# SCH_Weather_Station_2023-01-10.net
KiCad netlist of a schematic drawn in EasyEDA
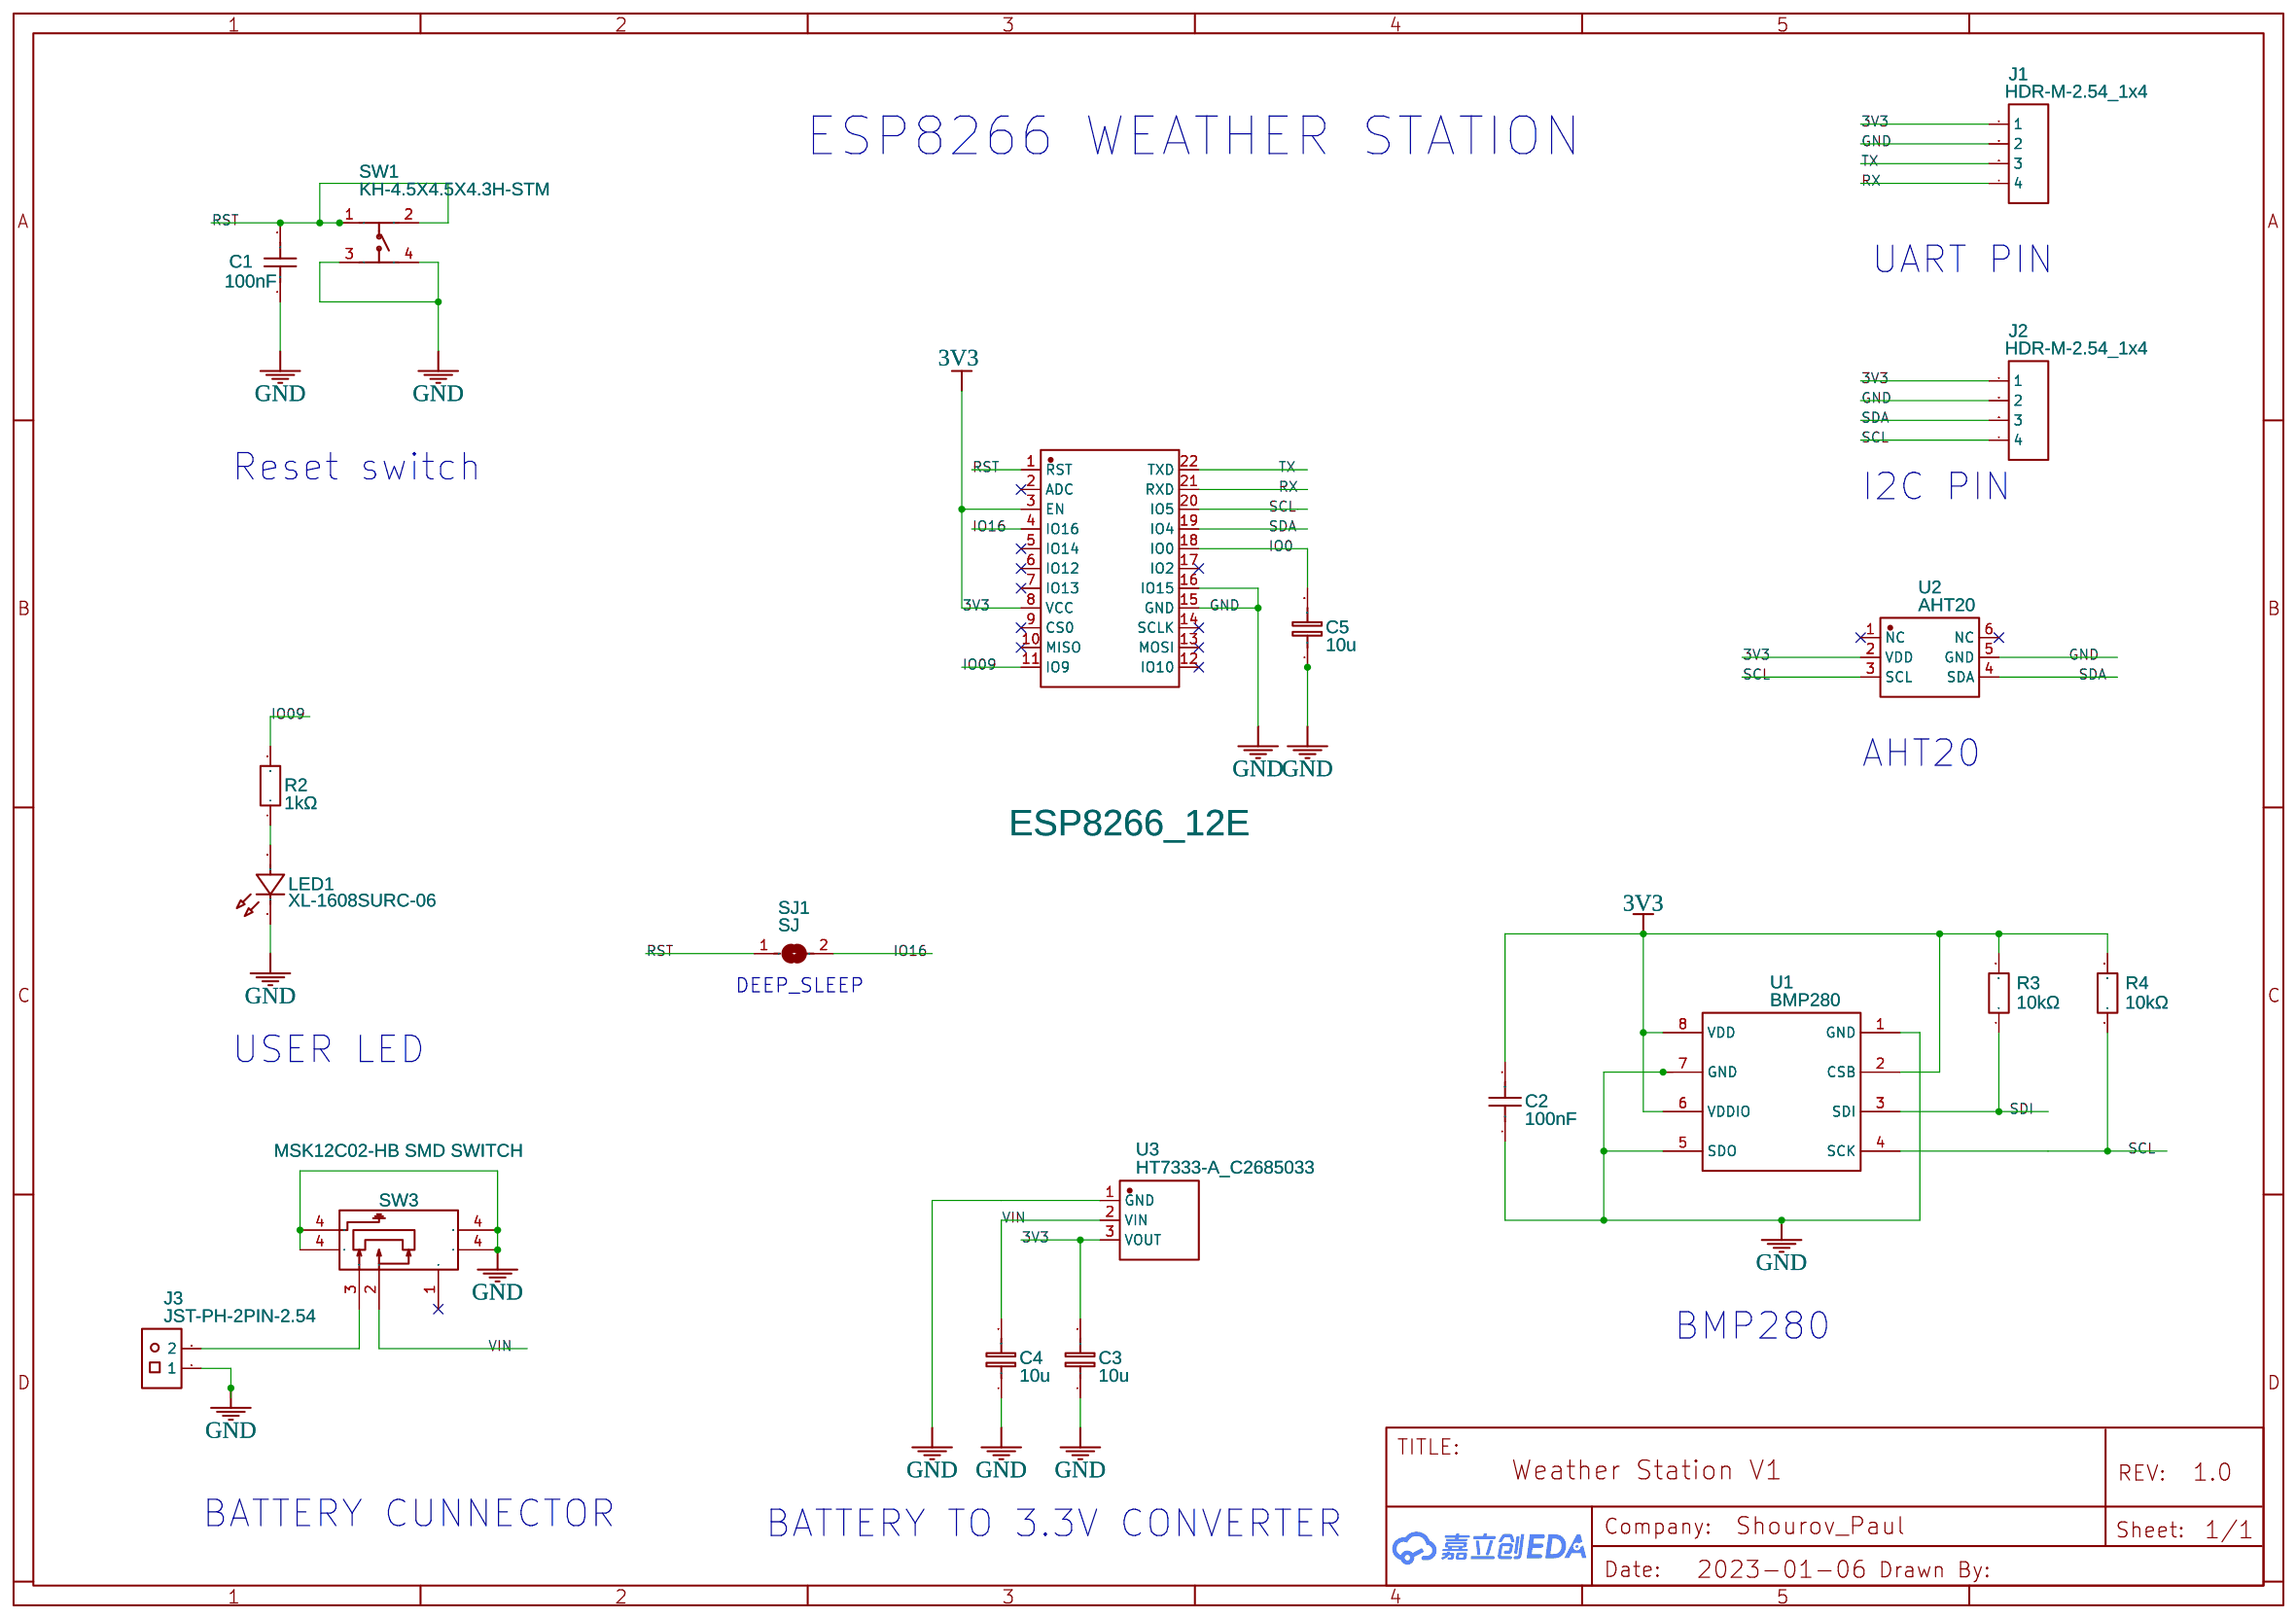
[diagram p0: schematic sheet]

(export (version "E")
  (design (tool "Eeschema 10.0.6"))
  (components
    (comp (ref "C1")
      (value "100nF")
      (fields
        (field (name "BOM_Manufacturer Part") "CC0603KRX7R6BB104")
        (field (name "BOM_Supplier Part") "C519438")
      )
      (libsource (lib "") (part "CC0603KRX7R6BB104"))
    )
    (comp (ref "C2")
      (value "100nF")
      (fields
        (field (name "BOM_Manufacturer Part") "CC0603KRX7R6BB104")
        (field (name "BOM_Supplier Part") "C519438")
      )
      (libsource (lib "") (part "CC0603KRX7R6BB104"))
    )
    (comp (ref "C3") (value "10u") (libsource (lib "") (part "C_0603_EU_2")))
    (comp (ref "C4") (value "10u") (libsource (lib "") (part "C_0603_EU_1")))
    (comp (ref "C5") (value "10u") (libsource (lib "") (part "C_0603_EU")))
    (comp (ref "ESP8266_12E")
      (value "2.4GHz")
      (fields (field (name "BOM_Manufacturer Part") "ESP-12E") (field (name "BOM_Supplier Part") "C89297"))
      (libsource (lib "") (part "ESP-12E"))
    )
    (comp (ref "J1")
      (value "HDR-M-2.54_1x4")
      (fields (field (name "BOM_Supplier Part") "C124378"))
      (libsource (lib "") (part "HDR-M-2.54_1x4"))
    )
    (comp (ref "J2")
      (value "HDR-M-2.54_1x4")
      (fields (field (name "BOM_Supplier Part") "C124378"))
      (libsource (lib "") (part "HDR-M-2.54_1x4"))
    )
    (comp (ref "J3") (value "JST-PH-2PIN-2.54") (libsource (lib "") (part "JST-PH-2PIN-2.54")))
    (comp (ref "LED1")
      (value "XL-1608SURC-06")
      (fields (field (name "BOM_Supplier Part") "C965799"))
      (libsource (lib "") (part "XL-1608SURC-06"))
    )
    (comp (ref "R2")
      (value "1kΩ")
      (fields
        (field (name "BOM_Manufacturer Part") "FRC0603J103TS")
        (field (name "BOM_Supplier Part") "C2930027")
      )
      (libsource (lib "") (part "FRC0603J103TS"))
    )
    (comp (ref "R3")
      (value "10kΩ")
      (fields
        (field (name "BOM_Manufacturer Part") "FRC0603J103TS")
        (field (name "BOM_Supplier Part") "C2930027")
      )
      (libsource (lib "") (part "FRC0603J103TS"))
    )
    (comp (ref "R4")
      (value "10kΩ")
      (fields
        (field (name "BOM_Manufacturer Part") "FRC0603J103TS")
        (field (name "BOM_Supplier Part") "C2930027")
      )
      (libsource (lib "") (part "FRC0603J103TS"))
    )
    (comp (ref "SJ1") (value "SJ") (libsource (lib "") (part "SJ")))
    (comp (ref "SW1")
      (value "KH-4.5X4.5X4.3H-STM")
      (fields (field (name "BOM_Supplier Part") "C2837550"))
      (libsource (lib "") (part "KH-4.5X4.5X4.3H-STM"))
    )
    (comp (ref "SW3")
      (value "MSK12C02-HB SMD SWITCH")
      (fields
        (field (name "BOM_Manufacturer Part") "MSK12C02-HB")
        (field (name "BOM_Supplier Part") "C431541")
      )
      (libsource (lib "") (part "MSK12C02-HB SMD SWITCH"))
    )
    (comp (ref "U1")
      (value "BMP280")
      (fields (field (name "BOM_Supplier Part") "C83291"))
      (libsource (lib "") (part "BMP280"))
    )
    (comp (ref "U2")
      (value "AHT20")
      (fields (field (name "BOM_Supplier Part") "C503357"))
      (libsource (lib "") (part "AHT20"))
    )
    (comp (ref "U3")
      (value "HT7333-A_C2685033")
      (fields (field (name "BOM_Manufacturer Part") "HT7333-A") (field (name "BOM_Supplier Part") "C2685033"))
      (libsource (lib "") (part "HT7333-A_C2685033"))
    )
  )
  (nets
    (net (code "1") (name "/IO0") (class "Default")
      (node (ref "C5") (pin "2") (pinfunction "2_2") (pintype "unspecified"))
      (node (ref "ESP8266_12E") (pin "18") (pinfunction "IO0_18") (pintype "unspecified"))
    )
    (net (code "2") (name "/IO09") (class "Default")
      (node (ref "ESP8266_12E") (pin "11") (pinfunction "IO9_11") (pintype "unspecified"))
      (node (ref "R2") (pin "2") (pinfunction "2_2") (pintype "unspecified"))
    )
    (net (code "3") (name "/IO16") (class "Default")
      (node (ref "ESP8266_12E") (pin "4") (pinfunction "IO16_4") (pintype "unspecified"))
      (node (ref "SJ1") (pin "2") (pinfunction "2_2") (pintype "bidirectional"))
    )
    (net (code "4") (name "/RST") (class "Default")
      (node (ref "C1") (pin "2") (pinfunction "2_2") (pintype "unspecified"))
      (node (ref "ESP8266_12E") (pin "1") (pinfunction "RST_1") (pintype "unspecified"))
      (node (ref "SJ1") (pin "1") (pinfunction "1_1") (pintype "bidirectional"))
      (node (ref "SW1") (pin "1") (pinfunction "1_1") (pintype "unspecified"))
      (node (ref "SW1") (pin "2") (pinfunction "2_2") (pintype "unspecified"))
    )
    (net (code "5") (name "/RX") (class "Default")
      (node (ref "ESP8266_12E") (pin "21") (pinfunction "RXD_21") (pintype "unspecified"))
      (node (ref "J1") (pin "4") (pinfunction "4_4") (pintype "unspecified"))
    )
    (net (code "6") (name "/SCL") (class "Default")
      (node (ref "ESP8266_12E") (pin "20") (pinfunction "IO5_20") (pintype "unspecified"))
      (node (ref "J2") (pin "4") (pinfunction "4_4") (pintype "unspecified"))
      (node (ref "R4") (pin "1") (pinfunction "1_1") (pintype "unspecified"))
      (node (ref "U1") (pin "4") (pinfunction "SCK_4") (pintype "unspecified"))
      (node (ref "U2") (pin "3") (pinfunction "SCL_3") (pintype "unspecified"))
    )
    (net (code "7") (name "/SDA") (class "Default")
      (node (ref "ESP8266_12E") (pin "19") (pinfunction "IO4_19") (pintype "unspecified"))
      (node (ref "J2") (pin "3") (pinfunction "3_3") (pintype "unspecified"))
      (node (ref "U2") (pin "4") (pinfunction "SDA_4") (pintype "unspecified"))
    )
    (net (code "8") (name "/SDI") (class "Default")
      (node (ref "R3") (pin "1") (pinfunction "1_1") (pintype "unspecified"))
      (node (ref "U1") (pin "3") (pinfunction "SDI_3") (pintype "unspecified"))
    )
    (net (code "9") (name "/TX") (class "Default")
      (node (ref "ESP8266_12E") (pin "22") (pinfunction "TXD_22") (pintype "unspecified"))
      (node (ref "J1") (pin "3") (pinfunction "3_3") (pintype "unspecified"))
    )
    (net (code "10") (name "/VIN") (class "Default")
      (node (ref "C4") (pin "2") (pinfunction "2_2") (pintype "unspecified"))
      (node (ref "SW3") (pin "2") (pinfunction "2_2") (pintype "unspecified"))
      (node (ref "U3") (pin "2") (pinfunction "VIN_2") (pintype "unspecified"))
    )
    (net (code "11") (name "3V3") (class "Default")
      (node (ref "C2") (pin "2") (pinfunction "2_2") (pintype "unspecified"))
      (node (ref "C3") (pin "2") (pinfunction "2_2") (pintype "unspecified"))
      (node (ref "ESP8266_12E") (pin "3") (pinfunction "EN_3") (pintype "unspecified"))
      (node (ref "ESP8266_12E") (pin "8") (pinfunction "VCC_8") (pintype "unspecified"))
      (node (ref "J1") (pin "1") (pinfunction "1_1") (pintype "unspecified"))
      (node (ref "J2") (pin "1") (pinfunction "1_1") (pintype "unspecified"))
      (node (ref "R3") (pin "2") (pinfunction "2_2") (pintype "unspecified"))
      (node (ref "R4") (pin "2") (pinfunction "2_2") (pintype "unspecified"))
      (node (ref "U1") (pin "2") (pinfunction "CSB_2") (pintype "unspecified"))
      (node (ref "U1") (pin "6") (pinfunction "VDDIO_6") (pintype "unspecified"))
      (node (ref "U1") (pin "8") (pinfunction "VDD_8") (pintype "unspecified"))
      (node (ref "U2") (pin "2") (pinfunction "VDD_2") (pintype "unspecified"))
      (node (ref "U3") (pin "3") (pinfunction "VOUT_3") (pintype "unspecified"))
    )
    (net (code "12") (name "GND") (class "Default")
      (node (ref "C1") (pin "1") (pinfunction "1_1") (pintype "unspecified"))
      (node (ref "C2") (pin "1") (pinfunction "1_1") (pintype "unspecified"))
      (node (ref "C3") (pin "1") (pinfunction "1_1") (pintype "unspecified"))
      (node (ref "C4") (pin "1") (pinfunction "1_1") (pintype "unspecified"))
      (node (ref "C5") (pin "1") (pinfunction "1_1") (pintype "unspecified"))
      (node (ref "ESP8266_12E") (pin "15") (pinfunction "GND_15") (pintype "unspecified"))
      (node (ref "ESP8266_12E") (pin "16") (pinfunction "IO15_16") (pintype "unspecified"))
      (node (ref "J1") (pin "2") (pinfunction "2_2") (pintype "unspecified"))
      (node (ref "J2") (pin "2") (pinfunction "2_2") (pintype "unspecified"))
      (node (ref "J3") (pin "1") (pinfunction "1_1") (pintype "unspecified"))
      (node (ref "LED1") (pin "1") (pinfunction "K_1") (pintype "unspecified"))
      (node (ref "SW1") (pin "3") (pinfunction "3_3") (pintype "unspecified"))
      (node (ref "SW1") (pin "4") (pinfunction "4_4") (pintype "unspecified"))
      (node (ref "SW3") (pin "4") (pinfunction "4_4") (pintype "unspecified"))
      (node (ref "U1") (pin "1") (pinfunction "GND_1") (pintype "unspecified"))
      (node (ref "U1") (pin "5") (pinfunction "SDO_5") (pintype "unspecified"))
      (node (ref "U1") (pin "7") (pinfunction "GND_7") (pintype "unspecified"))
      (node (ref "U2") (pin "5") (pinfunction "GND_5") (pintype "unspecified"))
      (node (ref "U3") (pin "1") (pinfunction "GND_1") (pintype "unspecified"))
    )
    (net (code "13") (name "Net-(J3-Pad2)") (class "Default")
      (node (ref "J3") (pin "2") (pinfunction "2_2") (pintype "unspecified"))
      (node (ref "SW3") (pin "3") (pinfunction "3_3") (pintype "unspecified"))
    )
    (net (code "14") (name "Net-(LED1-A)") (class "Default")
      (node (ref "LED1") (pin "2") (pinfunction "A_2") (pintype "unspecified"))
      (node (ref "R2") (pin "1") (pinfunction "1_1") (pintype "unspecified"))
    )
    (net (code "15") (name "unconnected-(ESP8266_12E-ADC-Pad2)") (class "Default")
      (node (ref "ESP8266_12E") (pin "2") (pinfunction "ADC_2") (pintype "unspecified+no_connect"))
    )
    (net (code "16") (name "unconnected-(ESP8266_12E-CS0-Pad9)") (class "Default")
      (node (ref "ESP8266_12E") (pin "9") (pinfunction "CS0_9") (pintype "unspecified+no_connect"))
    )
    (net (code "17") (name "unconnected-(ESP8266_12E-IO2-Pad17)") (class "Default")
      (node (ref "ESP8266_12E") (pin "17") (pinfunction "IO2_17") (pintype "unspecified+no_connect"))
    )
    (net (code "18") (name "unconnected-(ESP8266_12E-IO10-Pad12)") (class "Default")
      (node (ref "ESP8266_12E") (pin "12") (pinfunction "IO10_12") (pintype "unspecified+no_connect"))
    )
    (net (code "19") (name "unconnected-(ESP8266_12E-IO12-Pad6)") (class "Default")
      (node (ref "ESP8266_12E") (pin "6") (pinfunction "IO12_6") (pintype "unspecified+no_connect"))
    )
    (net (code "20") (name "unconnected-(ESP8266_12E-IO13-Pad7)") (class "Default")
      (node (ref "ESP8266_12E") (pin "7") (pinfunction "IO13_7") (pintype "unspecified+no_connect"))
    )
    (net (code "21") (name "unconnected-(ESP8266_12E-IO14-Pad5)") (class "Default")
      (node (ref "ESP8266_12E") (pin "5") (pinfunction "IO14_5") (pintype "unspecified+no_connect"))
    )
    (net (code "22") (name "unconnected-(ESP8266_12E-MISO-Pad10)") (class "Default")
      (node (ref "ESP8266_12E") (pin "10") (pinfunction "MISO_10") (pintype "unspecified+no_connect"))
    )
    (net (code "23") (name "unconnected-(ESP8266_12E-MOSI-Pad13)") (class "Default")
      (node (ref "ESP8266_12E") (pin "13") (pinfunction "MOSI_13") (pintype "unspecified+no_connect"))
    )
    (net (code "24") (name "unconnected-(ESP8266_12E-SCLK-Pad14)") (class "Default")
      (node (ref "ESP8266_12E") (pin "14") (pinfunction "SCLK_14") (pintype "unspecified+no_connect"))
    )
    (net (code "25") (name "unconnected-(SW3-Pad1)") (class "Default")
      (node (ref "SW3") (pin "1") (pinfunction "1_1") (pintype "unspecified+no_connect"))
    )
    (net (code "26") (name "unconnected-(U2-NC-Pad1)") (class "Default")
      (node (ref "U2") (pin "1") (pinfunction "NC_1") (pintype "unspecified+no_connect"))
    )
    (net (code "27") (name "unconnected-(U2-NC-Pad6)") (class "Default")
      (node (ref "U2") (pin "6") (pinfunction "NC_6") (pintype "unspecified+no_connect"))
    )
  )
)
